# logic.net
KiCad netlist of a schematic drawn in EAGLE
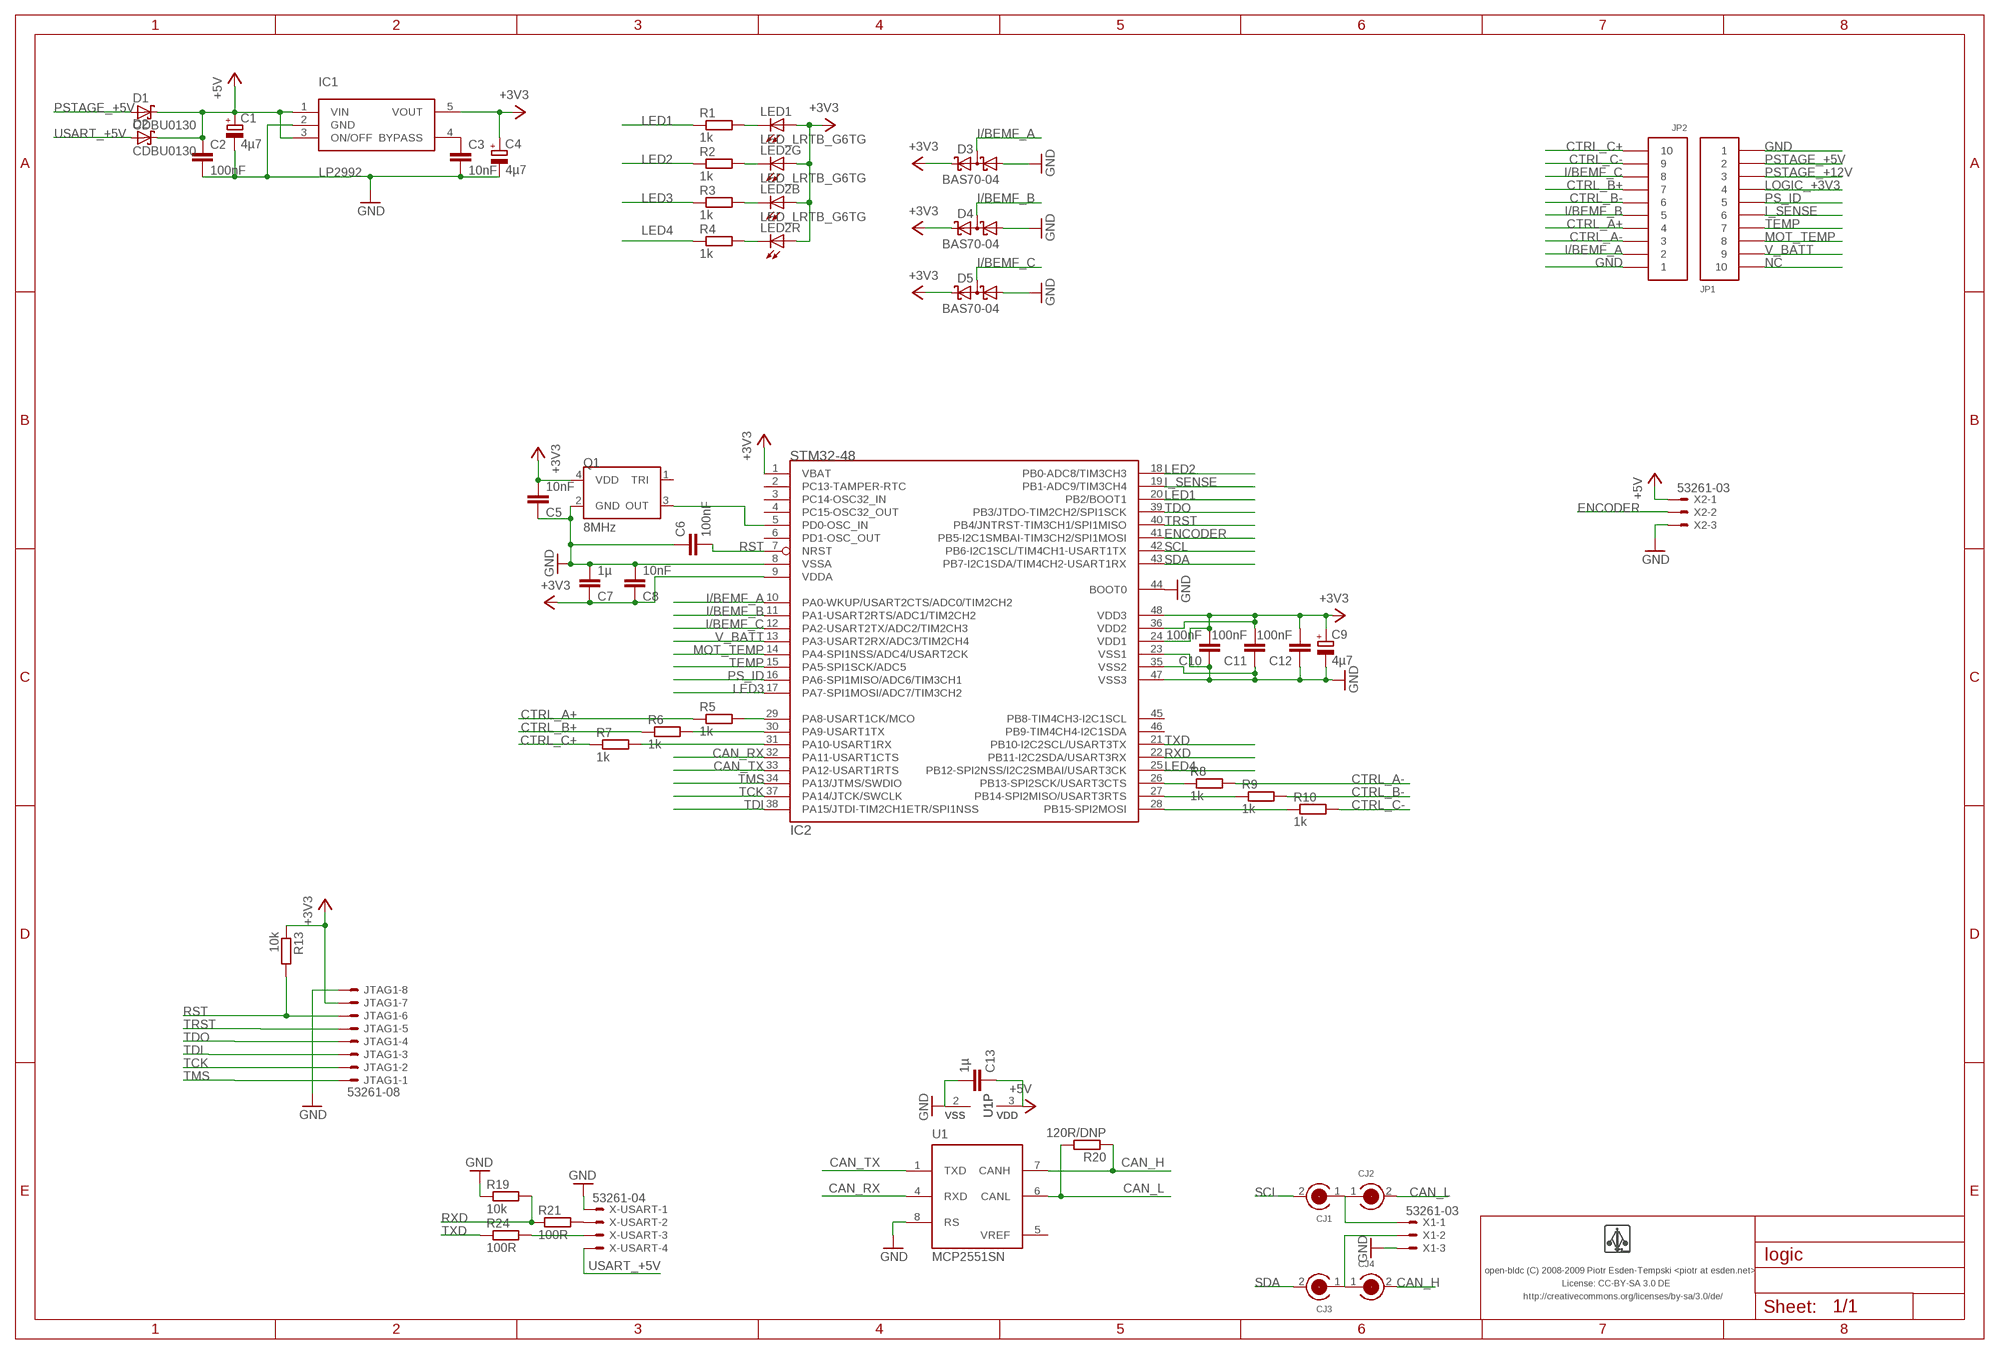
[diagram p0: schematic, sheet 1]

(export (version "E")
  (design (tool "Eeschema 10.0.6"))
  (components
    (comp (ref "C1")
      (value "4µ7")
      (footprint "eagle-import:A_3216-18R")
      (libsource (lib "eagle-import") (part "CPOL-EUA/3216-18R"))
    )
    (comp (ref "C2")
      (value "100nF")
      (footprint "eagle-import:C0603")
      (libsource (lib "eagle-import") (part "C-EUC0603"))
    )
    (comp (ref "C3")
      (value "10nF")
      (footprint "eagle-import:C0603")
      (libsource (lib "eagle-import") (part "C-EUC0603"))
    )
    (comp (ref "C4")
      (value "4µ7")
      (footprint "eagle-import:A_3216-18R")
      (libsource (lib "eagle-import") (part "CPOL-EUA/3216-18R"))
    )
    (comp (ref "C5")
      (value "10nF")
      (footprint "eagle-import:C0603")
      (libsource (lib "eagle-import") (part "C-EUC0603"))
    )
    (comp (ref "C6")
      (value "100nF")
      (footprint "eagle-import:C0603")
      (libsource (lib "eagle-import") (part "C-EUC0603"))
    )
    (comp (ref "C7")
      (value "1µ")
      (footprint "eagle-import:C0603")
      (libsource (lib "eagle-import") (part "C-EUC0603"))
    )
    (comp (ref "C8")
      (value "10nF")
      (footprint "eagle-import:C0603")
      (libsource (lib "eagle-import") (part "C-EUC0603"))
    )
    (comp (ref "C9")
      (value "4µ7")
      (footprint "eagle-import:A_3216-18R")
      (libsource (lib "eagle-import") (part "CPOL-EUA/3216-18R"))
    )
    (comp (ref "C10")
      (value "100nF")
      (footprint "eagle-import:C0603")
      (libsource (lib "eagle-import") (part "C-EUC0603"))
    )
    (comp (ref "C11")
      (value "100nF")
      (footprint "eagle-import:C0603")
      (libsource (lib "eagle-import") (part "C-EUC0603"))
    )
    (comp (ref "C12")
      (value "100nF")
      (footprint "eagle-import:C0603")
      (libsource (lib "eagle-import") (part "C-EUC0603"))
    )
    (comp (ref "C13")
      (value "1µ")
      (footprint "eagle-import:C0603")
      (libsource (lib "eagle-import") (part "C-EUC0603"))
    )
    (comp (ref "CJ1")
      (value "CIRC_JMP")
      (footprint "eagle-import:CIRC_JMP")
      (libsource (lib "eagle-import") (part "CIRC_JMP"))
    )
    (comp (ref "CJ2")
      (value "CIRC_JMP")
      (footprint "eagle-import:CIRC_JMP")
      (libsource (lib "eagle-import") (part "CIRC_JMP"))
    )
    (comp (ref "CJ3")
      (value "CIRC_JMP")
      (footprint "eagle-import:CIRC_JMP")
      (libsource (lib "eagle-import") (part "CIRC_JMP"))
    )
    (comp (ref "CJ4")
      (value "CIRC_JMP")
      (footprint "eagle-import:CIRC_JMP")
      (libsource (lib "eagle-import") (part "CIRC_JMP"))
    )
    (comp (ref "D1")
      (value "CDBU0130")
      (footprint "eagle-import:SOD523")
      (libsource (lib "eagle-import") (part "SCHOTTKY-DIODE0603"))
    )
    (comp (ref "D2")
      (value "CDBU0130")
      (footprint "eagle-import:SOD523")
      (libsource (lib "eagle-import") (part "SCHOTTKY-DIODE0603"))
    )
    (comp (ref "D3")
      (value "BAS70-04")
      (footprint "eagle-import:SOT23")
      (libsource (lib "eagle-import") (part "BAS70-04"))
    )
    (comp (ref "D4")
      (value "BAS70-04")
      (footprint "eagle-import:SOT23")
      (libsource (lib "eagle-import") (part "BAS70-04"))
    )
    (comp (ref "D5")
      (value "BAS70-04")
      (footprint "eagle-import:SOT23")
      (libsource (lib "eagle-import") (part "BAS70-04"))
    )
    (comp (ref "IC1")
      (value "LP2992")
      (footprint "eagle-import:SOT23-5")
      (libsource (lib "eagle-import") (part "LP2992"))
    )
    (comp (ref "IC2")
      (value "STM32-48")
      (footprint "eagle-import:LQFP48")
      (libsource (lib "eagle-import") (part "STM32-48"))
    )
    (comp (ref "JP1")
      (value "PIN_HDR_1.27MM_10")
      (footprint "eagle-import:PIN_HDR_1.27MM_10")
      (libsource (lib "eagle-import") (part "PIN_HDR_1.27MM_10_TH"))
    )
    (comp (ref "JP2")
      (value "PIN_HDR_1.27MM_10")
      (footprint "eagle-import:PIN_HDR_1.27MM_10")
      (libsource (lib "eagle-import") (part "PIN_HDR_1.27MM_10_TH"))
    )
    (comp (ref "JTAG1")
      (value "53261-08")
      (footprint "eagle-import:53261-08")
      (libsource (lib "eagle-import") (part "53?-08261"))
    )
    (comp (ref "LED1")
      (value "AMBER")
      (footprint "eagle-import:CHIP-LED0603")
      (libsource (lib "eagle-import") (part "LEDCHIP-LED0603"))
    )
    (comp (ref "LED2")
      (value "LED_LRTB_G6TG")
      (footprint "eagle-import:PLCC6")
      (libsource (lib "eagle-import") (part "LED_LRTB_G6TG"))
    )
    (comp (ref "Q1")
      (value "8MHz")
      (footprint "eagle-import:ASE_OSCILLATOR")
      (libsource (lib "eagle-import") (part "ASE_ASCILLATOR"))
    )
    (comp (ref "R1")
      (value "1k")
      (footprint "eagle-import:R0603")
      (libsource (lib "eagle-import") (part "R-EU_R0603"))
    )
    (comp (ref "R2")
      (value "1k")
      (footprint "eagle-import:R0603")
      (libsource (lib "eagle-import") (part "R-EU_R0603"))
    )
    (comp (ref "R3")
      (value "1k")
      (footprint "eagle-import:R0603")
      (libsource (lib "eagle-import") (part "R-EU_R0603"))
    )
    (comp (ref "R4")
      (value "1k")
      (footprint "eagle-import:R0603")
      (libsource (lib "eagle-import") (part "R-EU_R0603"))
    )
    (comp (ref "R5")
      (value "1k")
      (footprint "eagle-import:R0603")
      (libsource (lib "eagle-import") (part "R-EU_R0603"))
    )
    (comp (ref "R6")
      (value "1k")
      (footprint "eagle-import:R0603")
      (libsource (lib "eagle-import") (part "R-EU_R0603"))
    )
    (comp (ref "R7")
      (value "1k")
      (footprint "eagle-import:R0603")
      (libsource (lib "eagle-import") (part "R-EU_R0603"))
    )
    (comp (ref "R8")
      (value "1k")
      (footprint "eagle-import:R0603")
      (libsource (lib "eagle-import") (part "R-EU_R0603"))
    )
    (comp (ref "R9")
      (value "1k")
      (footprint "eagle-import:R0603")
      (libsource (lib "eagle-import") (part "R-EU_R0603"))
    )
    (comp (ref "R10")
      (value "1k")
      (footprint "eagle-import:R0603")
      (libsource (lib "eagle-import") (part "R-EU_R0603"))
    )
    (comp (ref "R13")
      (value "10k")
      (footprint "eagle-import:R0603")
      (libsource (lib "eagle-import") (part "resistor_R-EU_R0603"))
    )
    (comp (ref "R19")
      (value "10k")
      (footprint "eagle-import:R0603")
      (libsource (lib "eagle-import") (part "R-EU_R0603"))
    )
    (comp (ref "R20")
      (value "120R/DNP")
      (footprint "eagle-import:R0603")
      (libsource (lib "eagle-import") (part "R-EU_R0603"))
    )
    (comp (ref "R21")
      (value "100R")
      (footprint "eagle-import:R0603")
      (libsource (lib "eagle-import") (part "R-EU_R0603"))
    )
    (comp (ref "R24")
      (value "100R")
      (footprint "eagle-import:R0603")
      (libsource (lib "eagle-import") (part "R-EU_R0603"))
    )
    (comp (ref "U$1")
      (value "LOGO")
      (footprint "eagle-import:LOGO")
      (libsource (lib "eagle-import") (part "LOGO"))
    )
    (comp (ref "U1")
      (value "MCP2551SN")
      (footprint "eagle-import:SO-08")
      (libsource (lib "eagle-import") (part "MCP2551SN"))
    )
    (comp (ref "X-USART")
      (value "53261-04")
      (footprint "eagle-import:53261-04")
      (libsource (lib "eagle-import") (part "53?-04261"))
    )
    (comp (ref "X1")
      (value "53261-03")
      (footprint "eagle-import:53261-03")
      (libsource (lib "eagle-import") (part "53?-03261"))
    )
    (comp (ref "X2")
      (value "53261-03")
      (footprint "eagle-import:53261-03")
      (libsource (lib "eagle-import") (part "53?-03261"))
    )
  )
  (nets
    (net (code "1") (name "+3V3") (class "Default")
      (node (ref "C10") (pin "2") (pinfunction "2_2") (pintype "passive"))
      (node (ref "C11") (pin "2") (pinfunction "2_2") (pintype "passive"))
      (node (ref "C12") (pin "2") (pinfunction "2_2") (pintype "passive"))
      (node (ref "C4") (pin "+") (pinfunction "+_+") (pintype "passive"))
      (node (ref "C5") (pin "2") (pinfunction "2_2") (pintype "passive"))
      (node (ref "C7") (pin "1") (pinfunction "1_1") (pintype "passive"))
      (node (ref "C8") (pin "1") (pinfunction "1_1") (pintype "passive"))
      (node (ref "C9") (pin "+") (pinfunction "+_+") (pintype "passive"))
      (node (ref "D3") (pin "2") (pinfunction "C2_2") (pintype "passive"))
      (node (ref "D4") (pin "2") (pinfunction "C2_2") (pintype "passive"))
      (node (ref "D5") (pin "2") (pinfunction "C2_2") (pintype "passive"))
      (node (ref "IC1") (pin "5") (pinfunction "VOUT_5") (pintype "bidirectional"))
      (node (ref "IC2") (pin "1") (pinfunction "VBAT_1") (pintype "power_in"))
      (node (ref "IC2") (pin "24") (pinfunction "VDD1_24") (pintype "power_in"))
      (node (ref "IC2") (pin "36") (pinfunction "VDD2_36") (pintype "power_in"))
      (node (ref "IC2") (pin "48") (pinfunction "VDD3_48") (pintype "power_in"))
      (node (ref "IC2") (pin "9") (pinfunction "VDDA_9") (pintype "power_in"))
      (node (ref "JTAG1") (pin "7") (pinfunction "S_7") (pintype "passive"))
      (node (ref "LED1") (pin "A") (pinfunction "A_A") (pintype "passive"))
      (node (ref "LED2") (pin "A1") (pinfunction "A_A1") (pintype "passive"))
      (node (ref "LED2") (pin "A2") (pinfunction "A_A2") (pintype "passive"))
      (node (ref "LED2") (pin "A3") (pinfunction "A_A3") (pintype "passive"))
      (node (ref "Q1") (pin "4") (pinfunction "VDD_4") (pintype "power_in"))
      (node (ref "R13") (pin "1") (pinfunction "1_1") (pintype "passive"))
    )
    (net (code "2") (name "+5V") (class "Default")
      (node (ref "C1") (pin "+") (pinfunction "+_+") (pintype "passive"))
      (node (ref "C13") (pin "1") (pinfunction "1_1") (pintype "passive"))
      (node (ref "C2") (pin "1") (pinfunction "1_1") (pintype "passive"))
      (node (ref "D1") (pin "C") (pinfunction "C_C") (pintype "passive"))
      (node (ref "D2") (pin "C") (pinfunction "C_C") (pintype "passive"))
      (node (ref "IC1") (pin "1") (pinfunction "VIN_1") (pintype "bidirectional"))
      (node (ref "IC1") (pin "3") (pinfunction "ON/OFF_3") (pintype "bidirectional"))
      (node (ref "U1") (pin "3") (pinfunction "VDD_3") (pintype "power_in"))
      (node (ref "X2") (pin "1") (pinfunction "S_1") (pintype "passive"))
    )
    (net (code "3") (name "/CAN_H") (class "Default")
      (node (ref "CJ4") (pin "2") (pinfunction "P$2_2") (pintype "bidirectional"))
      (node (ref "R20") (pin "1") (pinfunction "1_1") (pintype "passive"))
      (node (ref "U1") (pin "7") (pinfunction "CANH_7") (pintype "bidirectional"))
    )
    (net (code "4") (name "/CAN_L") (class "Default")
      (node (ref "CJ2") (pin "2") (pinfunction "P$2_2") (pintype "bidirectional"))
      (node (ref "R20") (pin "2") (pinfunction "2_2") (pintype "passive"))
      (node (ref "U1") (pin "6") (pinfunction "CANL_6") (pintype "bidirectional"))
    )
    (net (code "5") (name "/CAN_RX") (class "Default")
      (node (ref "IC2") (pin "32") (pinfunction "PA11-USART1CTS_32") (pintype "bidirectional"))
      (node (ref "U1") (pin "4") (pinfunction "RXD_4") (pintype "output"))
    )
    (net (code "6") (name "/CAN_TX") (class "Default")
      (node (ref "IC2") (pin "33") (pinfunction "PA12-USART1RTS_33") (pintype "bidirectional"))
      (node (ref "U1") (pin "1") (pinfunction "TXD_1") (pintype "input"))
    )
    (net (code "7") (name "/CTRL_A+") (class "Default")
      (node (ref "JP2") (pin "P$4") (pinfunction "4_P$4") (pintype "bidirectional"))
      (node (ref "R5") (pin "1") (pinfunction "1_1") (pintype "passive"))
    )
    (net (code "8") (name "/CTRL_A-") (class "Default")
      (node (ref "JP2") (pin "P$3") (pinfunction "3_P$3") (pintype "bidirectional"))
      (node (ref "R8") (pin "2") (pinfunction "2_2") (pintype "passive"))
    )
    (net (code "9") (name "/CTRL_B+") (class "Default")
      (node (ref "JP2") (pin "P$7") (pinfunction "7_P$7") (pintype "bidirectional"))
      (node (ref "R6") (pin "1") (pinfunction "1_1") (pintype "passive"))
    )
    (net (code "10") (name "/CTRL_B-") (class "Default")
      (node (ref "JP2") (pin "P$6") (pinfunction "6_P$6") (pintype "bidirectional"))
      (node (ref "R9") (pin "2") (pinfunction "2_2") (pintype "passive"))
    )
    (net (code "11") (name "/CTRL_C+") (class "Default")
      (node (ref "JP2") (pin "P$10") (pinfunction "10_P$10") (pintype "bidirectional"))
      (node (ref "R7") (pin "1") (pinfunction "1_1") (pintype "passive"))
    )
    (net (code "12") (name "/CTRL_C-") (class "Default")
      (node (ref "JP2") (pin "P$9") (pinfunction "9_P$9") (pintype "bidirectional"))
      (node (ref "R10") (pin "2") (pinfunction "2_2") (pintype "passive"))
    )
    (net (code "13") (name "/ENCODER") (class "Default")
      (node (ref "IC2") (pin "41") (pinfunction "PB5-I2C1SMBAI-TIM3CH2/SPI1MOSI_41") (pintype "bidirectional"))
      (node (ref "X2") (pin "2") (pinfunction "S_2") (pintype "passive"))
    )
    (net (code "14") (name "/I_SENSE") (class "Default")
      (node (ref "IC2") (pin "19") (pinfunction "PB1-ADC9/TIM3CH4_19") (pintype "bidirectional"))
      (node (ref "JP1") (pin "P$6") (pinfunction "6_P$6") (pintype "bidirectional"))
    )
    (net (code "15") (name "/I{slash}BEMF_A") (class "Default")
      (node (ref "D3") (pin "3") (pinfunction "C1A2_3") (pintype "passive"))
      (node (ref "IC2") (pin "10") (pinfunction "PA0-WKUP/USART2CTS/ADC0/TIM2CH2_10") (pintype "bidirectional"))
      (node (ref "JP2") (pin "P$2") (pinfunction "2_P$2") (pintype "bidirectional"))
    )
    (net (code "16") (name "/I{slash}BEMF_B") (class "Default")
      (node (ref "D4") (pin "3") (pinfunction "C1A2_3") (pintype "passive"))
      (node (ref "IC2") (pin "11") (pinfunction "PA1-USART2RTS/ADC1/TIM2CH2_11") (pintype "bidirectional"))
      (node (ref "JP2") (pin "P$5") (pinfunction "5_P$5") (pintype "bidirectional"))
    )
    (net (code "17") (name "/I{slash}BEMF_C") (class "Default")
      (node (ref "D5") (pin "3") (pinfunction "C1A2_3") (pintype "passive"))
      (node (ref "IC2") (pin "12") (pinfunction "PA2-USART2TX/ADC2/TIM2CH3_12") (pintype "bidirectional"))
      (node (ref "JP2") (pin "P$8") (pinfunction "8_P$8") (pintype "bidirectional"))
    )
    (net (code "18") (name "/LED1") (class "Default")
      (node (ref "IC2") (pin "20") (pinfunction "PB2/BOOT1_20") (pintype "bidirectional"))
      (node (ref "R1") (pin "1") (pinfunction "1_1") (pintype "passive"))
    )
    (net (code "19") (name "/LED2") (class "Default")
      (node (ref "IC2") (pin "18") (pinfunction "PB0-ADC8/TIM3CH3_18") (pintype "bidirectional"))
      (node (ref "R2") (pin "1") (pinfunction "1_1") (pintype "passive"))
    )
    (net (code "20") (name "/LED3") (class "Default")
      (node (ref "IC2") (pin "17") (pinfunction "PA7-SPI1MOSI/ADC7/TIM3CH2_17") (pintype "bidirectional"))
      (node (ref "R3") (pin "1") (pinfunction "1_1") (pintype "passive"))
    )
    (net (code "21") (name "/LED4") (class "Default")
      (node (ref "IC2") (pin "25") (pinfunction "PB12-SPI2NSS/I2C2SMBAI/USART3CK_25") (pintype "bidirectional"))
      (node (ref "R4") (pin "1") (pinfunction "1_1") (pintype "passive"))
    )
    (net (code "22") (name "/LOGIC_+3V3") (class "Default")
      (node (ref "JP1") (pin "P$4") (pinfunction "4_P$4") (pintype "bidirectional"))
    )
    (net (code "23") (name "/MOT_TEMP") (class "Default")
      (node (ref "IC2") (pin "14") (pinfunction "PA4-SPI1NSS/ADC4/USART2CK_14") (pintype "bidirectional"))
      (node (ref "JP1") (pin "P$8") (pinfunction "8_P$8") (pintype "bidirectional"))
    )
    (net (code "24") (name "/NC") (class "Default")
      (node (ref "JP1") (pin "P$10") (pinfunction "10_P$10") (pintype "bidirectional"))
    )
    (net (code "25") (name "/PSTAGE_+5V") (class "Default")
      (node (ref "D1") (pin "A") (pinfunction "A_A") (pintype "passive"))
      (node (ref "JP1") (pin "P$2") (pinfunction "2_P$2") (pintype "bidirectional"))
    )
    (net (code "26") (name "/PSTAGE_+12V") (class "Default")
      (node (ref "JP1") (pin "P$3") (pinfunction "3_P$3") (pintype "bidirectional"))
    )
    (net (code "27") (name "/PS_ID") (class "Default")
      (node (ref "IC2") (pin "16") (pinfunction "PA6-SPI1MISO/ADC6/TIM3CH1_16") (pintype "bidirectional"))
      (node (ref "JP1") (pin "P$5") (pinfunction "5_P$5") (pintype "bidirectional"))
    )
    (net (code "28") (name "/RST") (class "Default")
      (node (ref "C6") (pin "2") (pinfunction "2_2") (pintype "passive"))
      (node (ref "IC2") (pin "7") (pinfunction "NRST_7") (pintype "bidirectional"))
      (node (ref "JTAG1") (pin "6") (pinfunction "S_6") (pintype "passive"))
      (node (ref "R13") (pin "2") (pinfunction "2_2") (pintype "passive"))
    )
    (net (code "29") (name "/RXD") (class "Default")
      (node (ref "IC2") (pin "22") (pinfunction "PB11-I2C2SDA/USART3RX_22") (pintype "bidirectional"))
      (node (ref "R19") (pin "2") (pinfunction "2_2") (pintype "passive"))
      (node (ref "R21") (pin "1") (pinfunction "1_1") (pintype "passive"))
    )
    (net (code "30") (name "/SCL") (class "Default")
      (node (ref "CJ1") (pin "2") (pinfunction "P$2_2") (pintype "bidirectional"))
      (node (ref "IC2") (pin "42") (pinfunction "PB6-I2C1SCL/TIM4CH1-USART1TX_42") (pintype "bidirectional"))
    )
    (net (code "31") (name "/SDA") (class "Default")
      (node (ref "CJ3") (pin "2") (pinfunction "P$2_2") (pintype "bidirectional"))
      (node (ref "IC2") (pin "43") (pinfunction "PB7-I2C1SDA/TIM4CH2-USART1RX_43") (pintype "bidirectional"))
    )
    (net (code "32") (name "/TCK") (class "Default")
      (node (ref "IC2") (pin "37") (pinfunction "PA14/JTCK/SWCLK_37") (pintype "bidirectional"))
      (node (ref "JTAG1") (pin "2") (pinfunction "S_2") (pintype "passive"))
    )
    (net (code "33") (name "/TDI") (class "Default")
      (node (ref "IC2") (pin "38") (pinfunction "PA15/JTDI-TIM2CH1ETR/SPI1NSS_38") (pintype "bidirectional"))
      (node (ref "JTAG1") (pin "3") (pinfunction "S_3") (pintype "passive"))
    )
    (net (code "34") (name "/TDO") (class "Default")
      (node (ref "IC2") (pin "39") (pinfunction "PB3/JTDO-TIM2CH2/SPI1SCK_39") (pintype "bidirectional"))
      (node (ref "JTAG1") (pin "4") (pinfunction "S_4") (pintype "passive"))
    )
    (net (code "35") (name "/TEMP") (class "Default")
      (node (ref "IC2") (pin "15") (pinfunction "PA5-SPI1SCK/ADC5_15") (pintype "bidirectional"))
      (node (ref "JP1") (pin "P$7") (pinfunction "7_P$7") (pintype "bidirectional"))
    )
    (net (code "36") (name "/TMS") (class "Default")
      (node (ref "IC2") (pin "34") (pinfunction "PA13/JTMS/SWDIO_34") (pintype "bidirectional"))
      (node (ref "JTAG1") (pin "1") (pinfunction "S_1") (pintype "passive"))
    )
    (net (code "37") (name "/TRST") (class "Default")
      (node (ref "IC2") (pin "40") (pinfunction "PB4/JNTRST-TIM3CH1/SPI1MISO_40") (pintype "bidirectional"))
      (node (ref "JTAG1") (pin "5") (pinfunction "S_5") (pintype "passive"))
    )
    (net (code "38") (name "/TXD") (class "Default")
      (node (ref "IC2") (pin "21") (pinfunction "PB10-I2C2SCL/USART3TX_21") (pintype "bidirectional"))
      (node (ref "R24") (pin "1") (pinfunction "1_1") (pintype "passive"))
    )
    (net (code "39") (name "/USART_+5V") (class "Default")
      (node (ref "D2") (pin "A") (pinfunction "A_A") (pintype "passive"))
      (node (ref "X-USART") (pin "4") (pinfunction "S_4") (pintype "passive"))
    )
    (net (code "40") (name "/VREF") (class "Default")
      (node (ref "U1") (pin "5") (pinfunction "VREF_5") (pintype "power_in"))
    )
    (net (code "41") (name "/V_BATT") (class "Default")
      (node (ref "IC2") (pin "13") (pinfunction "PA3-USART2RX/ADC3/TIM2CH4_13") (pintype "bidirectional"))
      (node (ref "JP1") (pin "P$9") (pinfunction "9_P$9") (pintype "bidirectional"))
    )
    (net (code "42") (name "GND") (class "Default")
      (node (ref "C1") (pin "-") (pinfunction "-_-") (pintype "passive"))
      (node (ref "C10") (pin "1") (pinfunction "1_1") (pintype "passive"))
      (node (ref "C11") (pin "1") (pinfunction "1_1") (pintype "passive"))
      (node (ref "C12") (pin "1") (pinfunction "1_1") (pintype "passive"))
      (node (ref "C13") (pin "2") (pinfunction "2_2") (pintype "passive"))
      (node (ref "C2") (pin "2") (pinfunction "2_2") (pintype "passive"))
      (node (ref "C3") (pin "2") (pinfunction "2_2") (pintype "passive"))
      (node (ref "C4") (pin "-") (pinfunction "-_-") (pintype "passive"))
      (node (ref "C5") (pin "1") (pinfunction "1_1") (pintype "passive"))
      (node (ref "C6") (pin "1") (pinfunction "1_1") (pintype "passive"))
      (node (ref "C7") (pin "2") (pinfunction "2_2") (pintype "passive"))
      (node (ref "C8") (pin "2") (pinfunction "2_2") (pintype "passive"))
      (node (ref "C9") (pin "-") (pinfunction "-_-") (pintype "passive"))
      (node (ref "D3") (pin "1") (pinfunction "A1_1") (pintype "passive"))
      (node (ref "D4") (pin "1") (pinfunction "A1_1") (pintype "passive"))
      (node (ref "D5") (pin "1") (pinfunction "A1_1") (pintype "passive"))
      (node (ref "IC1") (pin "2") (pinfunction "GND_2") (pintype "bidirectional"))
      (node (ref "IC2") (pin "23") (pinfunction "VSS1_23") (pintype "power_in"))
      (node (ref "IC2") (pin "35") (pinfunction "VSS2_35") (pintype "power_in"))
      (node (ref "IC2") (pin "44") (pinfunction "BOOT0_44") (pintype "input"))
      (node (ref "IC2") (pin "47") (pinfunction "VSS3_47") (pintype "power_in"))
      (node (ref "IC2") (pin "8") (pinfunction "VSSA_8") (pintype "power_in"))
      (node (ref "JP1") (pin "P$1") (pinfunction "1_P$1") (pintype "bidirectional"))
      (node (ref "JP2") (pin "P$1") (pinfunction "1_P$1") (pintype "bidirectional"))
      (node (ref "JTAG1") (pin "8") (pinfunction "S_8") (pintype "passive"))
      (node (ref "Q1") (pin "2") (pinfunction "GND_2") (pintype "power_in"))
      (node (ref "R19") (pin "1") (pinfunction "1_1") (pintype "passive"))
      (node (ref "U1") (pin "2") (pinfunction "VSS_2") (pintype "power_in"))
      (node (ref "U1") (pin "8") (pinfunction "RS_8") (pintype "input"))
      (node (ref "X-USART") (pin "1") (pinfunction "S_1") (pintype "passive"))
      (node (ref "X1") (pin "3") (pinfunction "S_3") (pintype "passive"))
      (node (ref "X2") (pin "3") (pinfunction "S_3") (pintype "passive"))
    )
    (net (code "43") (name "Net-(CJ1-P$1)") (class "Default")
      (node (ref "CJ1") (pin "1") (pinfunction "P$1_1") (pintype "bidirectional"))
      (node (ref "CJ2") (pin "1") (pinfunction "P$1_1") (pintype "bidirectional"))
      (node (ref "X1") (pin "1") (pinfunction "S_1") (pintype "passive"))
    )
    (net (code "44") (name "Net-(CJ3-P$1)") (class "Default")
      (node (ref "CJ3") (pin "1") (pinfunction "P$1_1") (pintype "bidirectional"))
      (node (ref "CJ4") (pin "1") (pinfunction "P$1_1") (pintype "bidirectional"))
      (node (ref "X1") (pin "2") (pinfunction "S_2") (pintype "passive"))
    )
    (net (code "45") (name "Net-(IC1-BYPASS)") (class "Default")
      (node (ref "C3") (pin "1") (pinfunction "1_1") (pintype "passive"))
      (node (ref "IC1") (pin "4") (pinfunction "BYPASS_4") (pintype "bidirectional"))
    )
    (net (code "46") (name "Net-(IC2-PA8-USART1CK{slash}MCO)") (class "Default")
      (node (ref "IC2") (pin "29") (pinfunction "PA8-USART1CK/MCO_29") (pintype "bidirectional"))
      (node (ref "R5") (pin "2") (pinfunction "2_2") (pintype "passive"))
    )
    (net (code "47") (name "Net-(IC2-PA9-USART1TX)") (class "Default")
      (node (ref "IC2") (pin "30") (pinfunction "PA9-USART1TX_30") (pintype "bidirectional"))
      (node (ref "R6") (pin "2") (pinfunction "2_2") (pintype "passive"))
    )
    (net (code "48") (name "Net-(IC2-PA10-USART1RX)") (class "Default")
      (node (ref "IC2") (pin "31") (pinfunction "PA10-USART1RX_31") (pintype "bidirectional"))
      (node (ref "R7") (pin "2") (pinfunction "2_2") (pintype "passive"))
    )
    (net (code "49") (name "Net-(IC2-PB13-SPI2SCK{slash}USART3CTS)") (class "Default")
      (node (ref "IC2") (pin "26") (pinfunction "PB13-SPI2SCK/USART3CTS_26") (pintype "bidirectional"))
      (node (ref "R8") (pin "1") (pinfunction "1_1") (pintype "passive"))
    )
    (net (code "50") (name "Net-(IC2-PB14-SPI2MISO{slash}USART3RTS)") (class "Default")
      (node (ref "IC2") (pin "27") (pinfunction "PB14-SPI2MISO/USART3RTS_27") (pintype "bidirectional"))
      (node (ref "R9") (pin "1") (pinfunction "1_1") (pintype "passive"))
    )
    (net (code "51") (name "Net-(IC2-PB15-SPI2MOSI)") (class "Default")
      (node (ref "IC2") (pin "28") (pinfunction "PB15-SPI2MOSI_28") (pintype "bidirectional"))
      (node (ref "R10") (pin "1") (pinfunction "1_1") (pintype "passive"))
    )
    (net (code "52") (name "Net-(IC2-PD0-OSC_IN)") (class "Default")
      (node (ref "IC2") (pin "5") (pinfunction "PD0-OSC_IN_5") (pintype "input"))
      (node (ref "Q1") (pin "3") (pinfunction "OUT_3") (pintype "output"))
    )
    (net (code "53") (name "Net-(LED1-PadC)") (class "Default")
      (node (ref "LED1") (pin "C") (pinfunction "C_C") (pintype "passive"))
      (node (ref "R1") (pin "2") (pinfunction "2_2") (pintype "passive"))
    )
    (net (code "54") (name "Net-(LED2A-C)") (class "Default")
      (node (ref "LED2") (pin "C3") (pinfunction "C_C3") (pintype "passive"))
      (node (ref "R3") (pin "2") (pinfunction "2_2") (pintype "passive"))
    )
    (net (code "55") (name "Net-(LED2B-C)") (class "Default")
      (node (ref "LED2") (pin "C2") (pinfunction "C_C2") (pintype "passive"))
      (node (ref "R2") (pin "2") (pinfunction "2_2") (pintype "passive"))
    )
    (net (code "56") (name "Net-(LED2C-C)") (class "Default")
      (node (ref "LED2") (pin "C1") (pinfunction "C_C1") (pintype "passive"))
      (node (ref "R4") (pin "2") (pinfunction "2_2") (pintype "passive"))
    )
    (net (code "57") (name "Net-(X-USARTB-S)") (class "Default")
      (node (ref "R21") (pin "2") (pinfunction "2_2") (pintype "passive"))
      (node (ref "X-USART") (pin "2") (pinfunction "S_2") (pintype "passive"))
    )
    (net (code "58") (name "Net-(X-USARTC-S)") (class "Default")
      (node (ref "R24") (pin "2") (pinfunction "2_2") (pintype "passive"))
      (node (ref "X-USART") (pin "3") (pinfunction "S_3") (pintype "passive"))
    )
    (net (code "59") (name "unconnected-(IC2-PB8-TIM4CH3-I2C1SCL-Pad45)") (class "Default")
      (node (ref "IC2") (pin "45") (pinfunction "PB8-TIM4CH3-I2C1SCL_45") (pintype "bidirectional"))
    )
    (net (code "60") (name "unconnected-(IC2-PB9-TIM4CH4-I2C1SDA-Pad46)") (class "Default")
      (node (ref "IC2") (pin "46") (pinfunction "PB9-TIM4CH4-I2C1SDA_46") (pintype "bidirectional"))
    )
    (net (code "61") (name "unconnected-(IC2-PC13-TAMPER-RTC-Pad2)") (class "Default")
      (node (ref "IC2") (pin "2") (pinfunction "PC13-TAMPER-RTC_2") (pintype "bidirectional"))
    )
    (net (code "62") (name "unconnected-(IC2-PC14-OSC32_IN-Pad3)") (class "Default")
      (node (ref "IC2") (pin "3") (pinfunction "PC14-OSC32_IN_3") (pintype "bidirectional"))
    )
    (net (code "63") (name "unconnected-(IC2-PC15-OSC32_OUT-Pad4)") (class "Default")
      (node (ref "IC2") (pin "4") (pinfunction "PC15-OSC32_OUT_4") (pintype "bidirectional"))
    )
    (net (code "64") (name "unconnected-(IC2-PD1-OSC_OUT-Pad6)") (class "Default")
      (node (ref "IC2") (pin "6") (pinfunction "PD1-OSC_OUT_6") (pintype "output"))
    )
    (net (code "65") (name "unconnected-(Q1-TRI-Pad1)") (class "Default")
      (node (ref "Q1") (pin "1") (pinfunction "TRI_1") (pintype "output"))
    )
  )
)
